# VDA.net
KiCad netlist of a schematic drawn in EAGLE
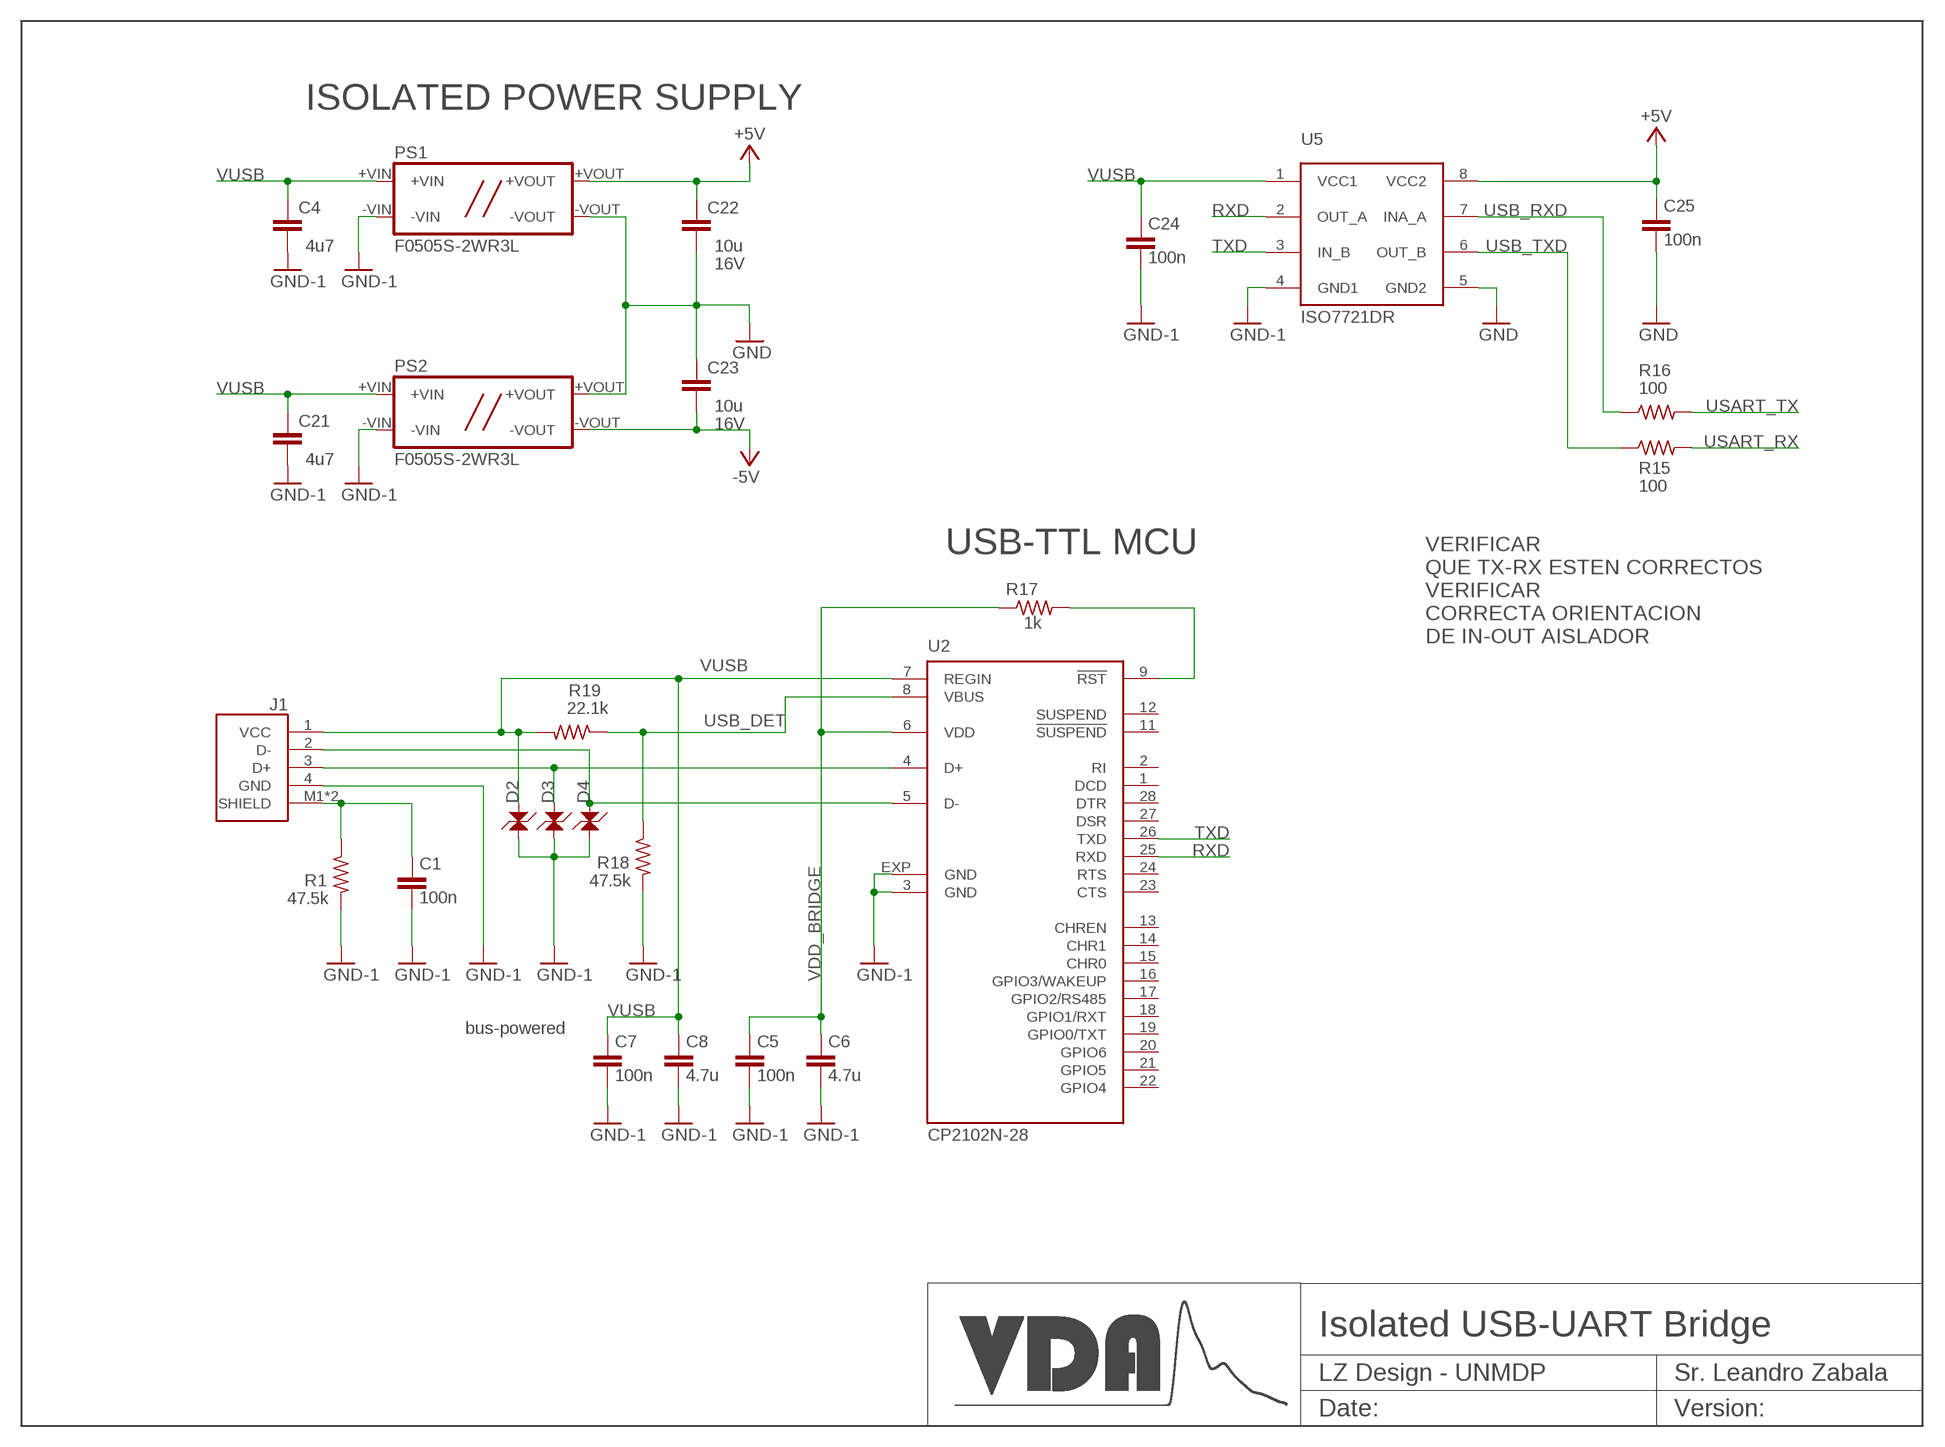
[diagram p0: schematic, sheet 1]
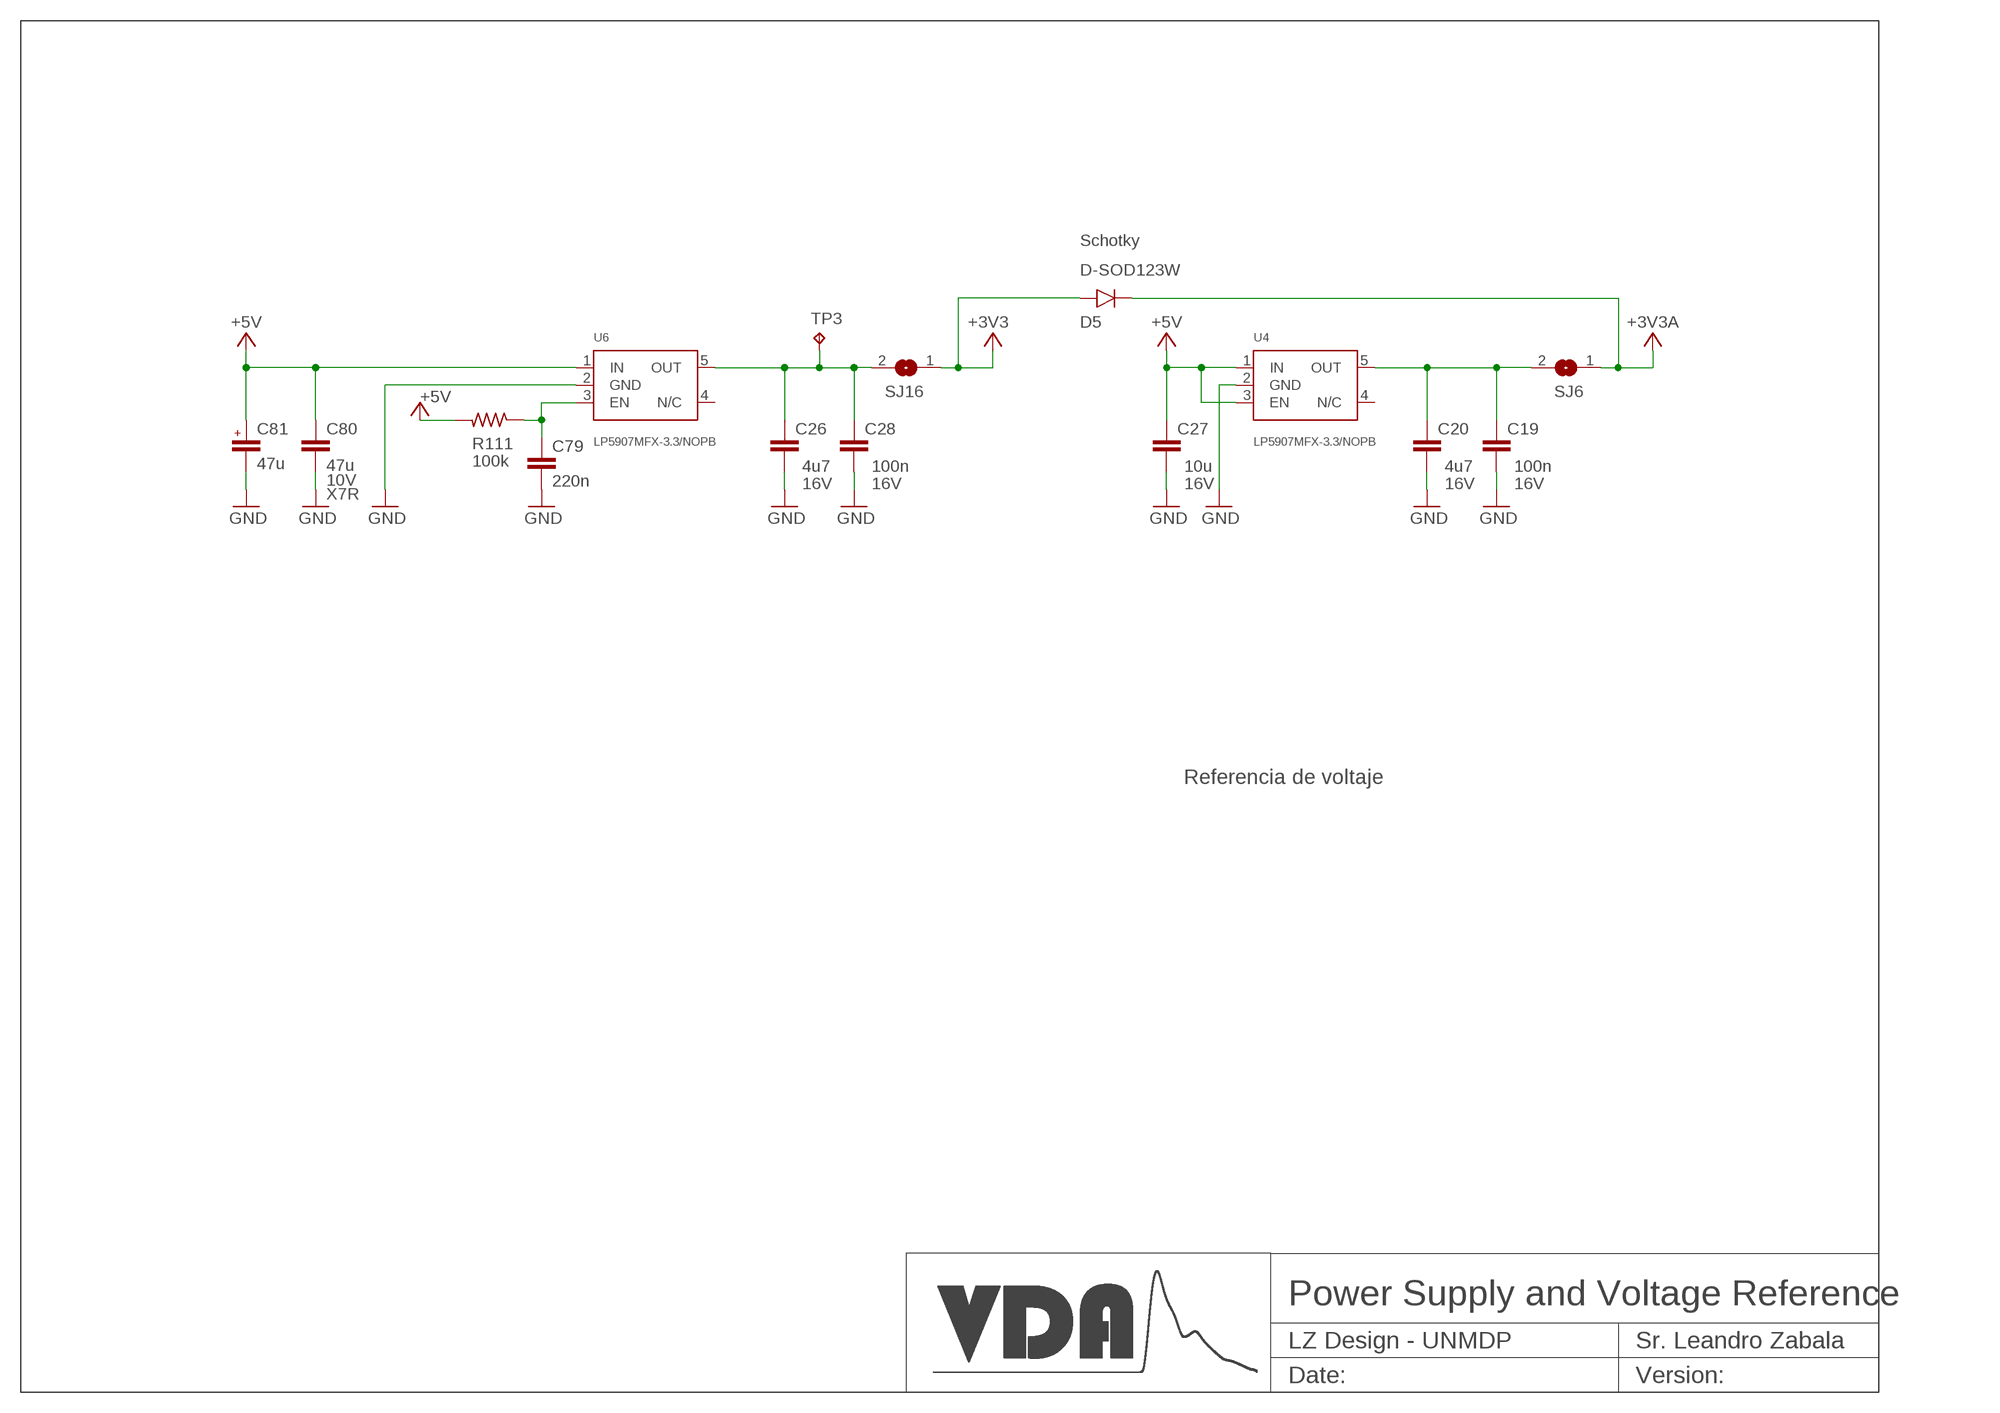
[diagram p1: schematic, sheet 2]
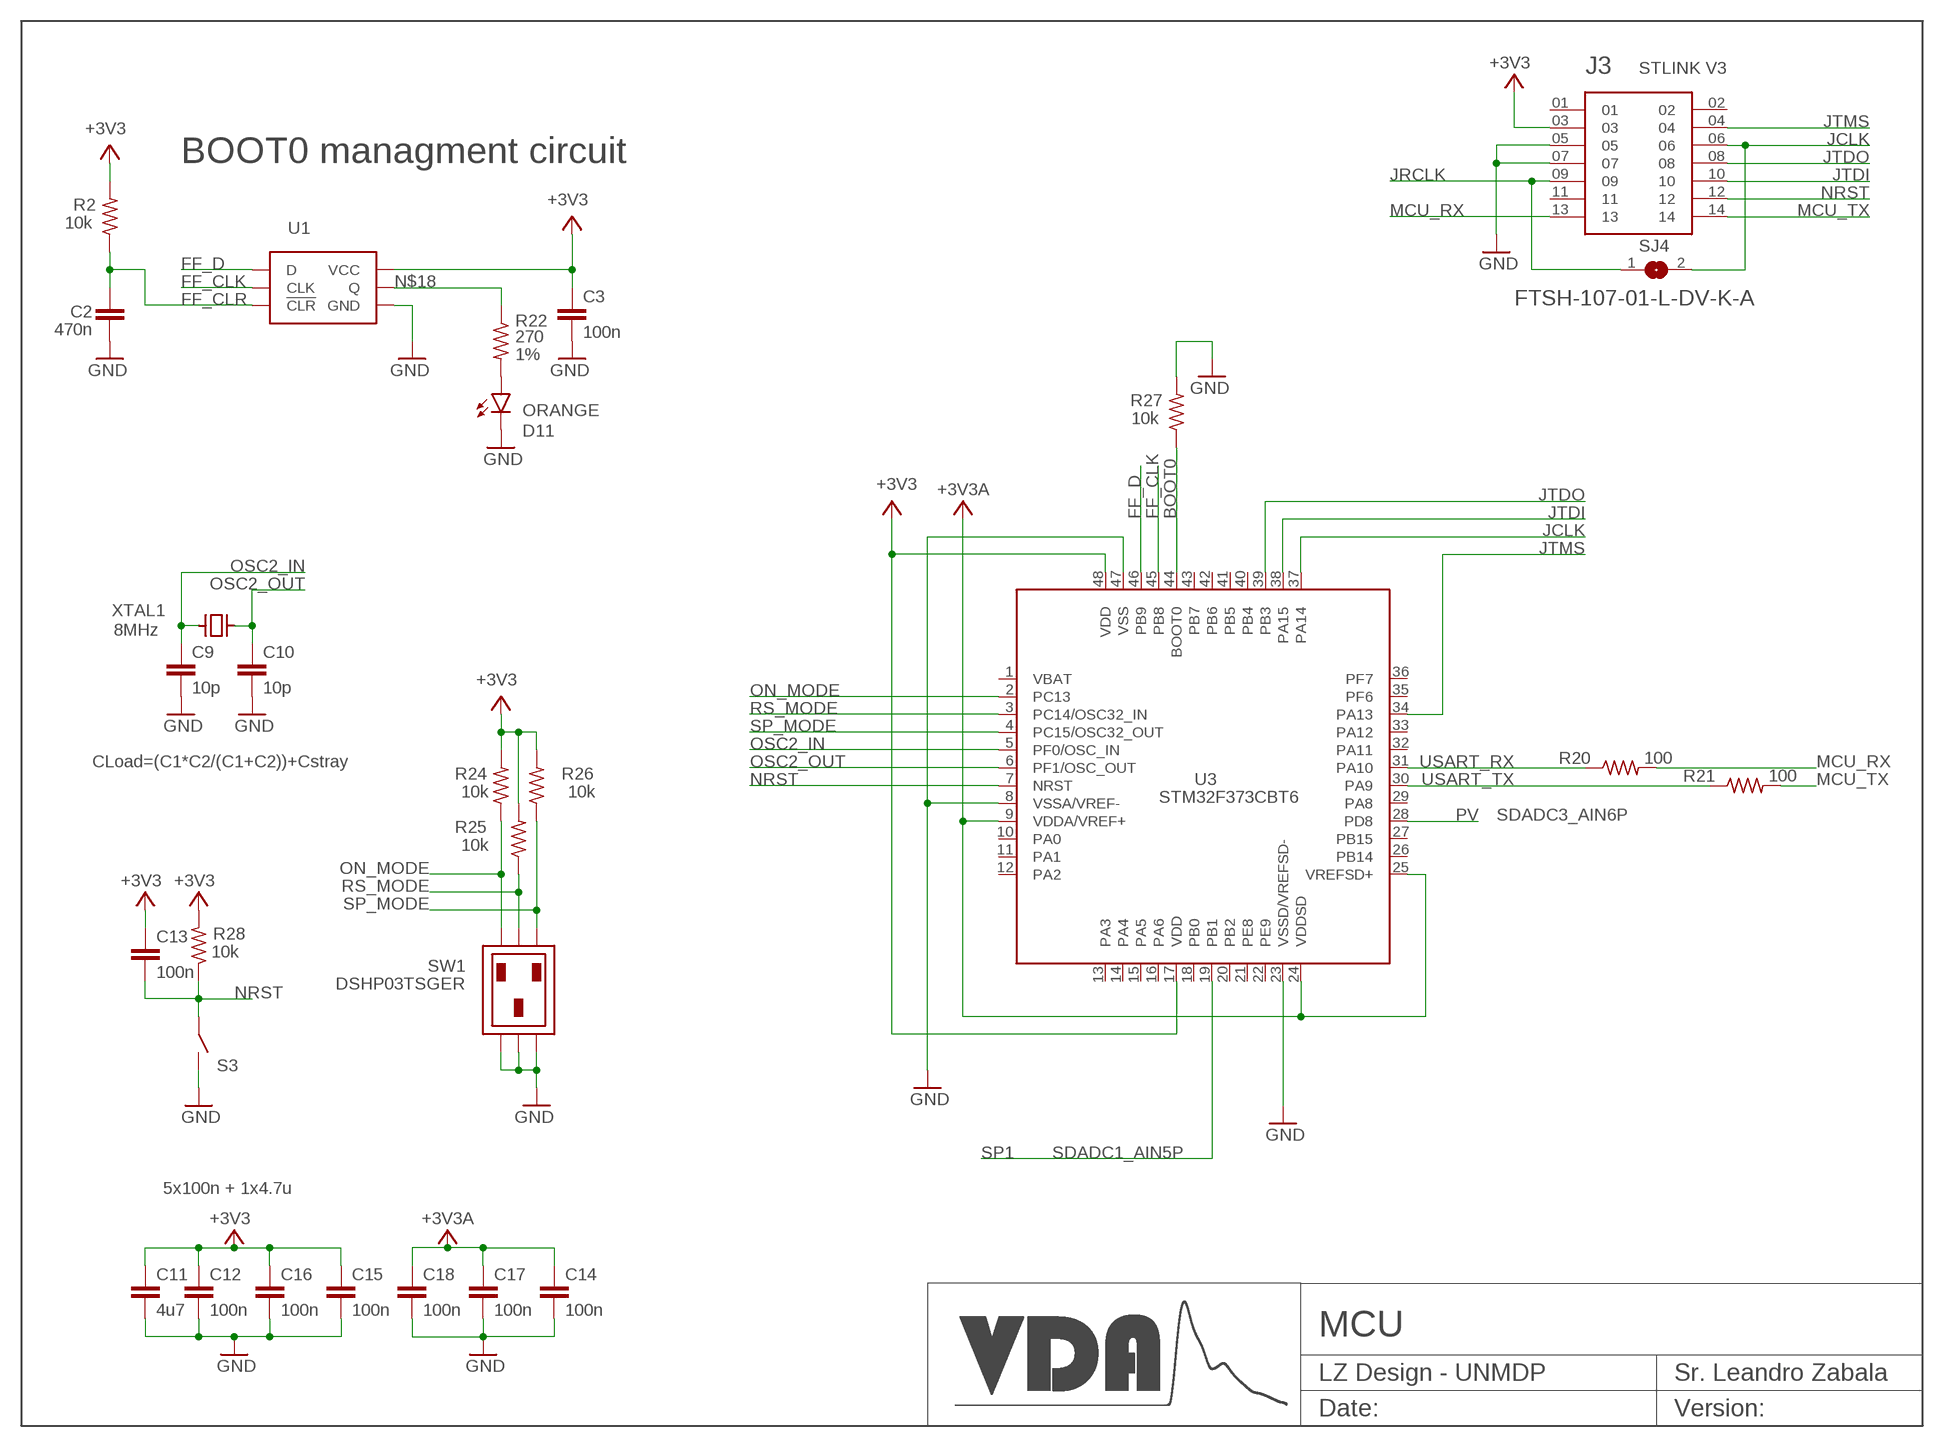
[diagram p2: schematic, sheet 3]
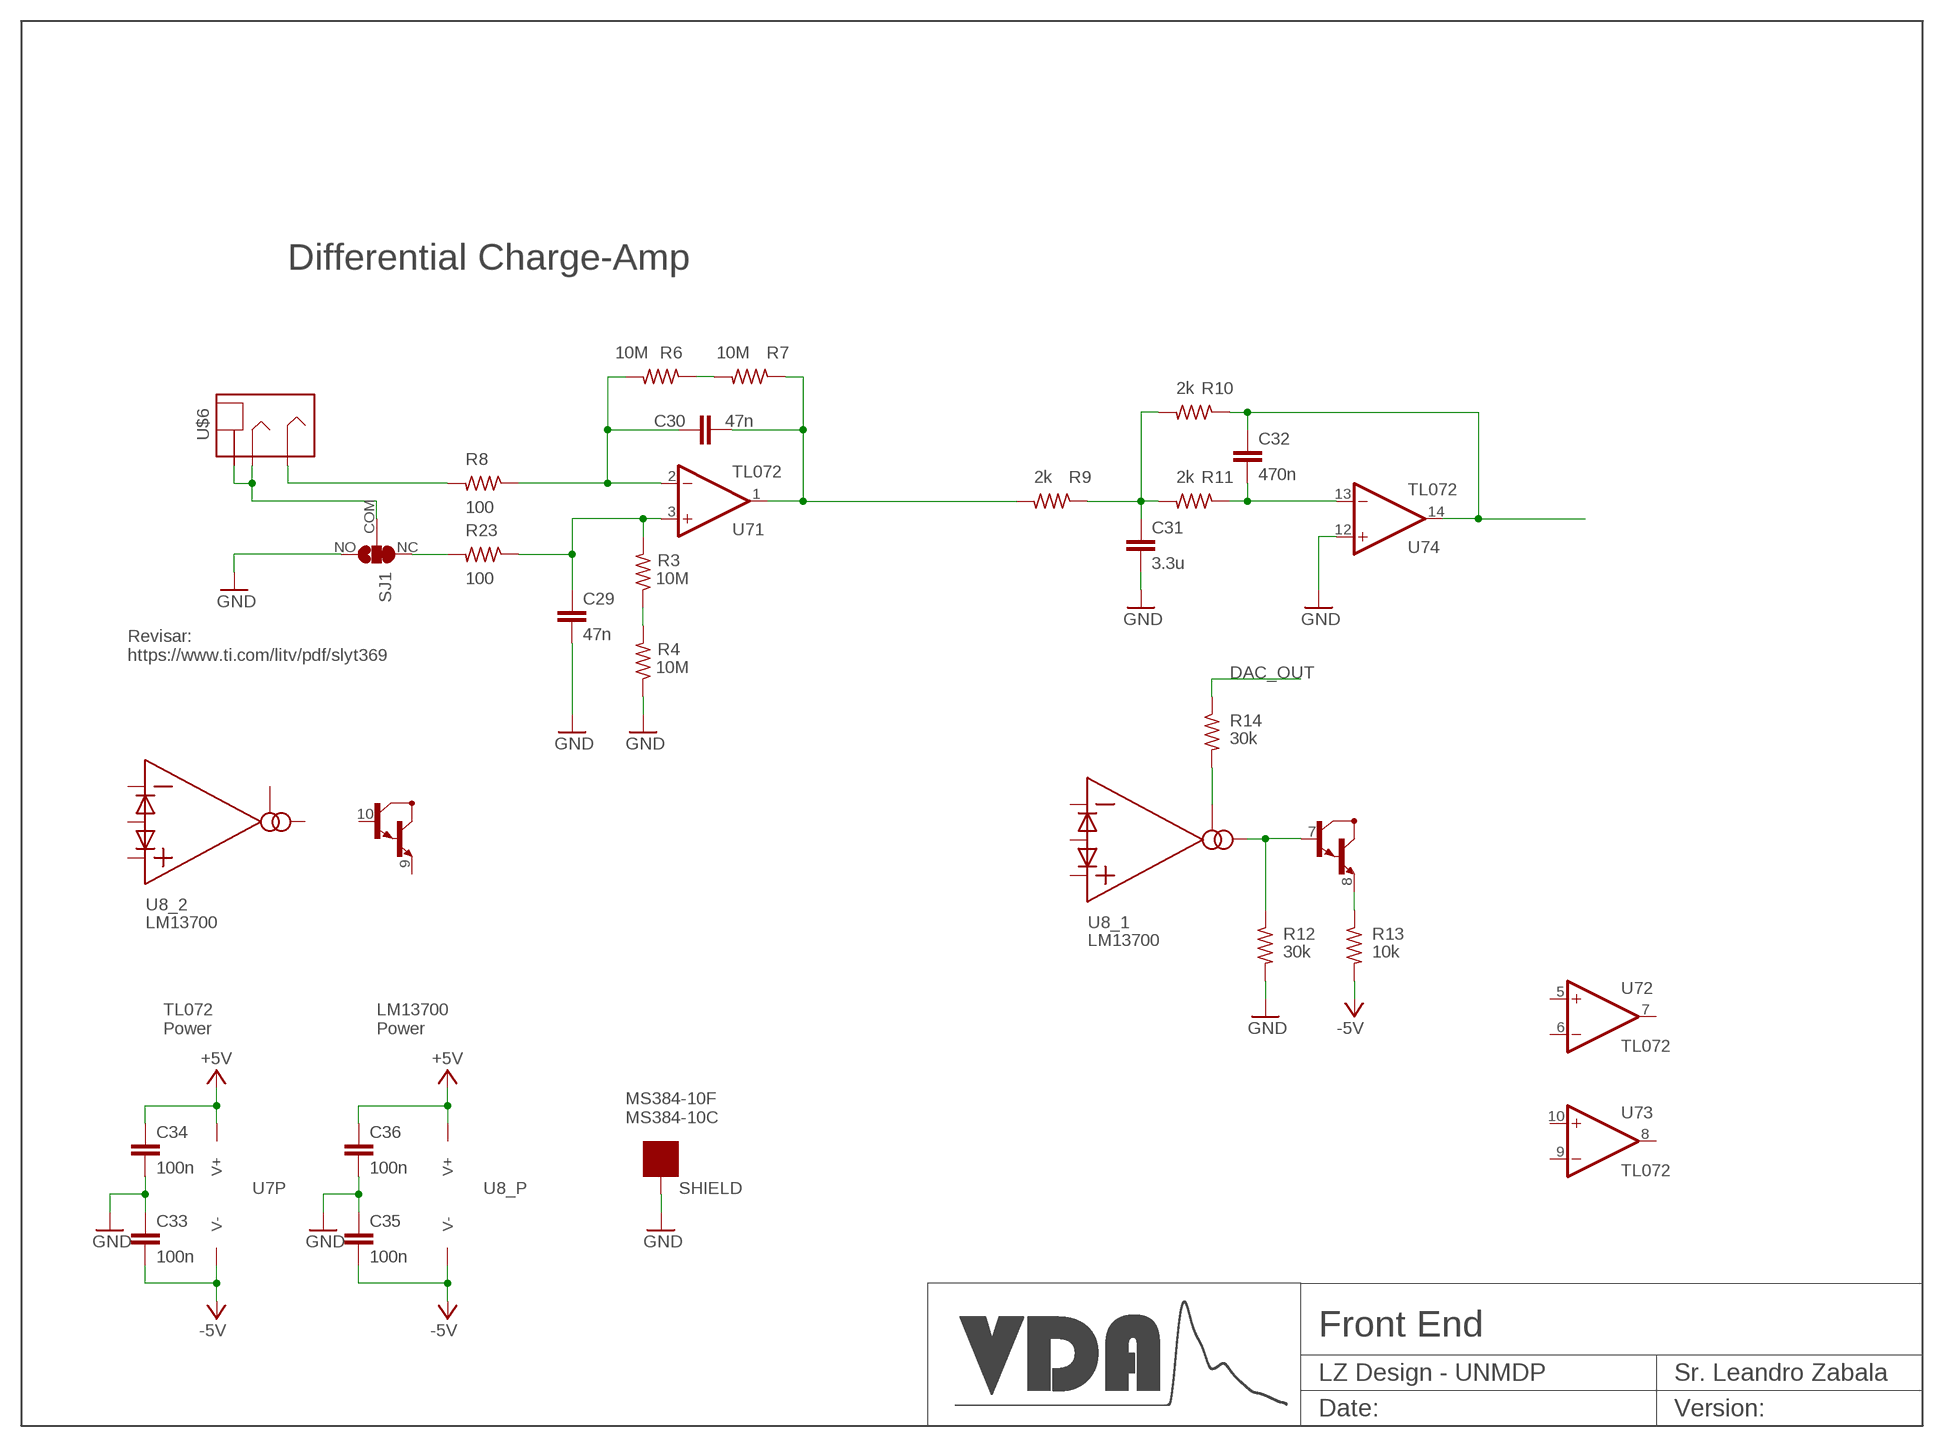
[diagram p3: schematic, sheet 4]
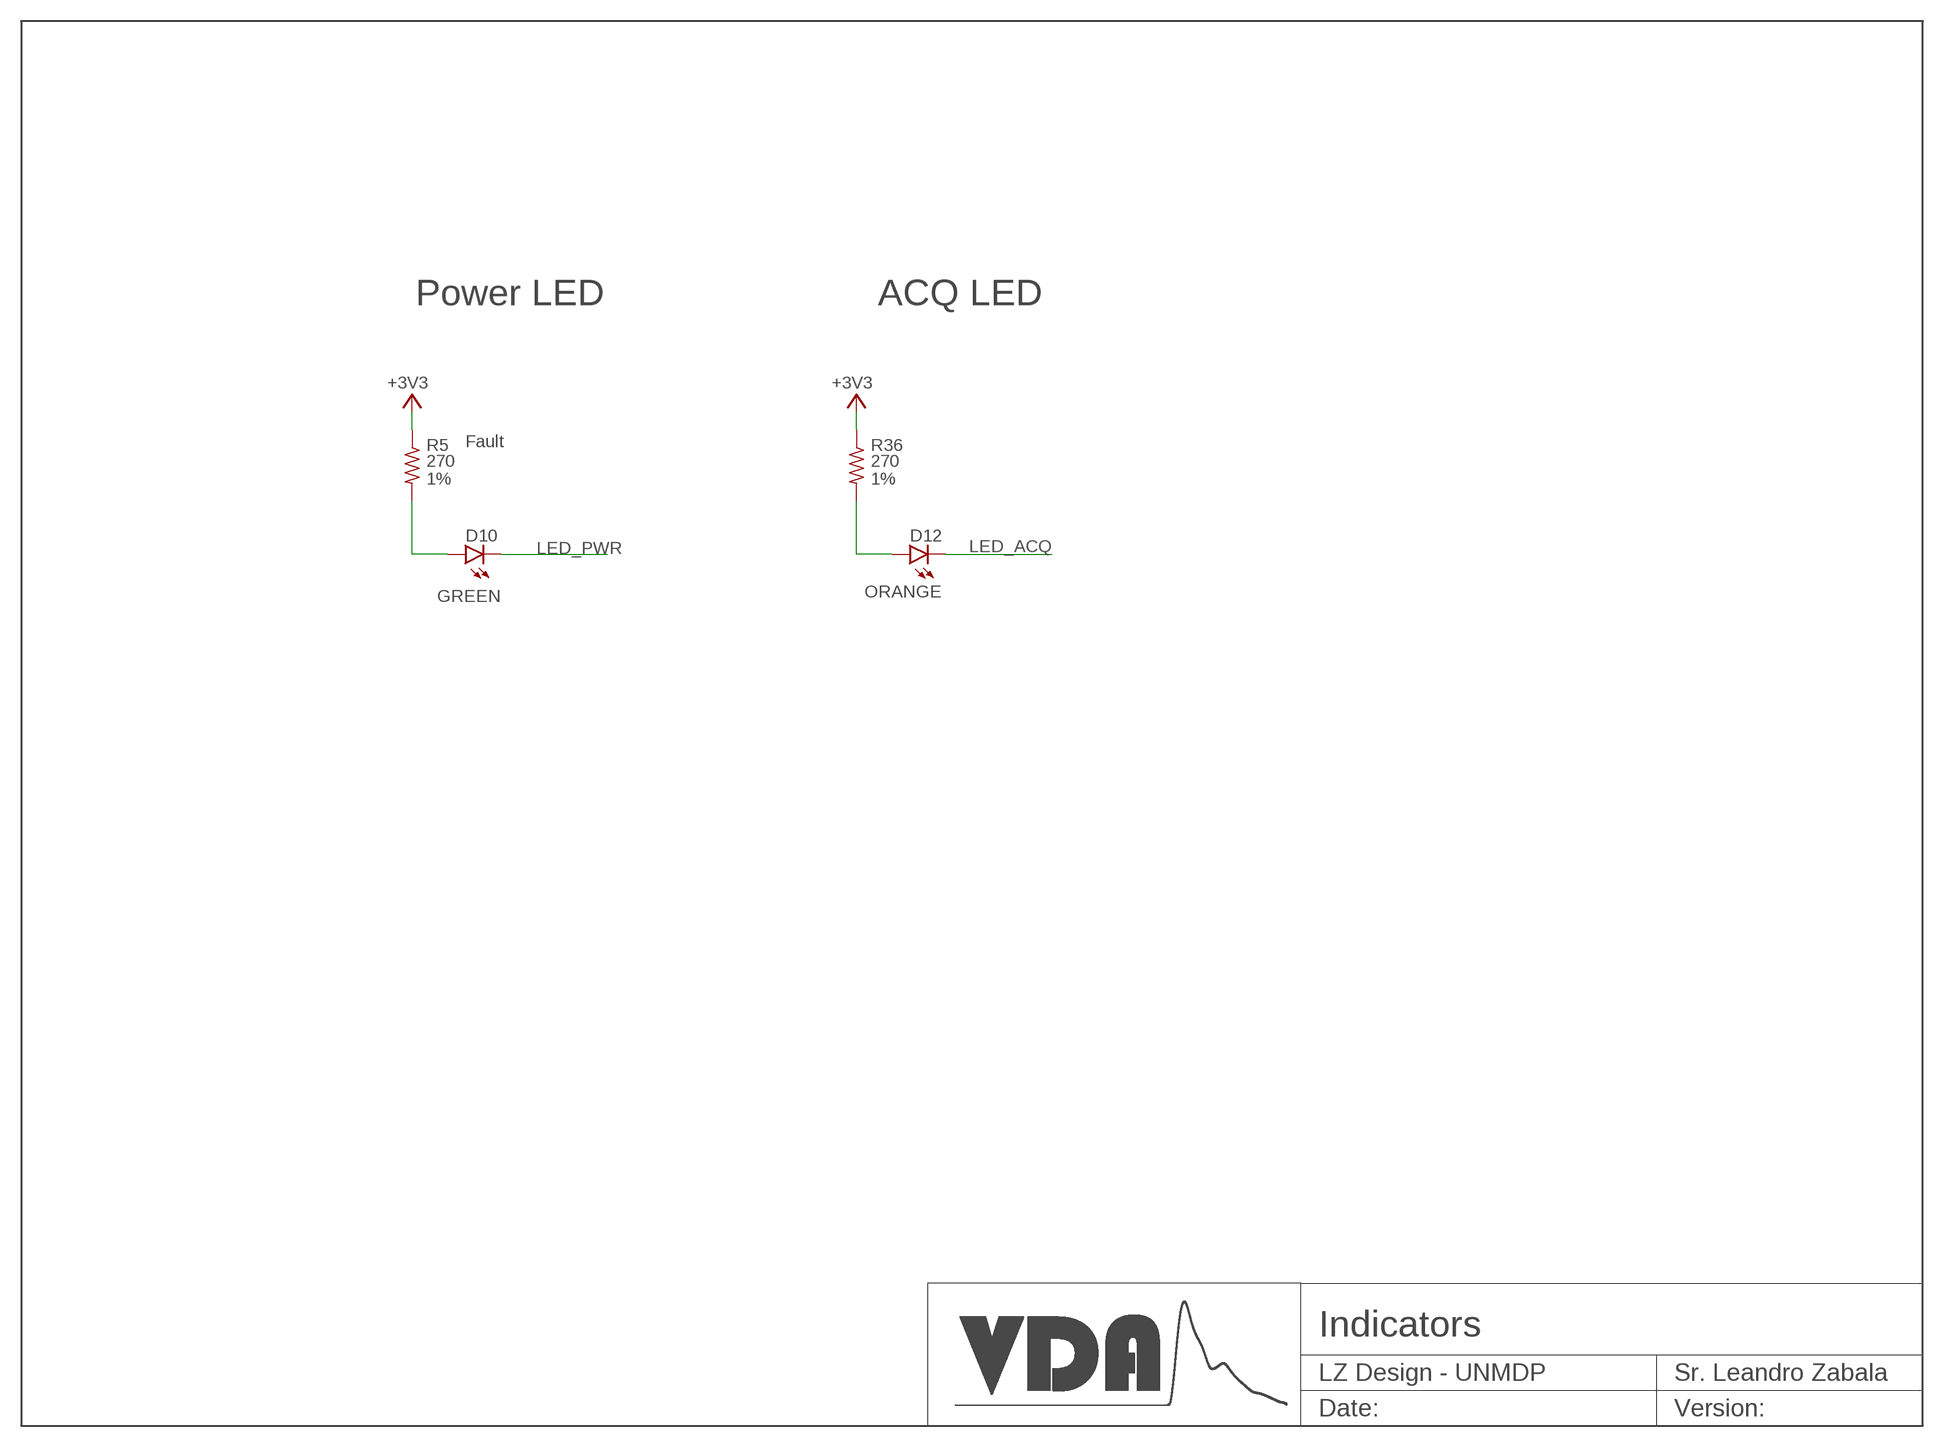
[diagram p4: schematic, sheet 5]

(export (version "E")
  (design (tool "Eeschema 10.0.6"))
  (components
    (comp (ref "D10")
      (value "GREEN")
      (footprint "eagle-import:LED_0603_ARROW")
      (libsource (lib "eagle-import") (part "LED_0603_ARROW"))
    )
    (comp (ref "D12")
      (value "ORANGE")
      (footprint "eagle-import:LED_0603_ARROW")
      (libsource (lib "eagle-import") (part "LED_0603_ARROW"))
    )
    (comp (ref "R5")
      (value "270")
      (footprint "eagle-import:R_0402")
      (fields (field (name "TOL") "1%"))
      (libsource (lib "eagle-import") (part "R_0402"))
    )
    (comp (ref "R36")
      (value "270")
      (footprint "eagle-import:R_0402")
      (fields (field (name "TOL") "1%"))
      (libsource (lib "eagle-import") (part "R_0402"))
    )
    (comp (ref "C1")
      (value "100n")
      (footprint "eagle-import:C_0603")
      (libsource (lib "eagle-import") (part "C_0603"))
    )
    (comp (ref "C4")
      (value "4u7")
      (footprint "eagle-import:C_0603")
      (fields (field (name "V") "16V"))
      (libsource (lib "eagle-import") (part "C_0603"))
    )
    (comp (ref "C5")
      (value "100n")
      (footprint "eagle-import:C_0603")
      (libsource (lib "eagle-import") (part "C_0603"))
    )
    (comp (ref "C6")
      (value "4.7u")
      (footprint "eagle-import:C_0805")
      (libsource (lib "eagle-import") (part "C_0805"))
    )
    (comp (ref "C7")
      (value "100n")
      (footprint "eagle-import:C_0603")
      (libsource (lib "eagle-import") (part "C_0603"))
    )
    (comp (ref "C8")
      (value "4.7u")
      (footprint "eagle-import:C_0805")
      (libsource (lib "eagle-import") (part "C_0805"))
    )
    (comp (ref "C21")
      (value "4u7")
      (footprint "eagle-import:C_0603")
      (fields (field (name "V") "16V"))
      (libsource (lib "eagle-import") (part "C_0603"))
    )
    (comp (ref "C22")
      (value "10u")
      (footprint "eagle-import:C_0603")
      (fields (field (name "V") "16V"))
      (libsource (lib "eagle-import") (part "C_0603"))
    )
    (comp (ref "C23")
      (value "10u")
      (footprint "eagle-import:C_0603")
      (fields (field (name "V") "16V"))
      (libsource (lib "eagle-import") (part "C_0603"))
    )
    (comp (ref "C24")
      (value "100n")
      (footprint "eagle-import:C_0603")
      (libsource (lib "eagle-import") (part "C_0603"))
    )
    (comp (ref "C25")
      (value "100n")
      (footprint "eagle-import:C_0603")
      (libsource (lib "eagle-import") (part "C_0603"))
    )
    (comp (ref "D2")
      (value "LESD5D5.0CT1G")
      (footprint "eagle-import:SOD523")
      (libsource (lib "eagle-import") (part "LESD5D5.0CT1G"))
    )
    (comp (ref "D3")
      (value "LESD5D5.0CT1G")
      (footprint "eagle-import:SOD523")
      (libsource (lib "eagle-import") (part "LESD5D5.0CT1G"))
    )
    (comp (ref "D4")
      (value "LESD5D5.0CT1G")
      (footprint "eagle-import:SOD523")
      (libsource (lib "eagle-import") (part "LESD5D5.0CT1G"))
    )
    (comp (ref "J1")
      (value "USB-2.0")
      (footprint "eagle-import:USB-B")
      (libsource (lib "eagle-import") (part "USB-2.0"))
    )
    (comp (ref "PS1")
      (value "F0505S-2WR3L")
      (footprint "eagle-import:0505S-2WR3")
      (libsource (lib "eagle-import") (part "ISOLATED_DCDC"))
    )
    (comp (ref "PS2")
      (value "F0505S-2WR3L")
      (footprint "eagle-import:0505S-2WR3")
      (libsource (lib "eagle-import") (part "ISOLATED_DCDC"))
    )
    (comp (ref "R1")
      (value "47.5k")
      (footprint "eagle-import:R0402")
      (libsource (lib "eagle-import") (part "R-US_R0402"))
    )
    (comp (ref "R15")
      (value "100")
      (footprint "eagle-import:R_0603")
      (libsource (lib "eagle-import") (part "R_0603"))
    )
    (comp (ref "R16")
      (value "100")
      (footprint "eagle-import:R_0603")
      (libsource (lib "eagle-import") (part "R_0603"))
    )
    (comp (ref "R17")
      (value "1k")
      (footprint "eagle-import:R0402")
      (libsource (lib "eagle-import") (part "R-US_R0402"))
    )
    (comp (ref "R18")
      (value "47.5k")
      (footprint "eagle-import:R0402")
      (libsource (lib "eagle-import") (part "R-US_R0402"))
    )
    (comp (ref "R19")
      (value "22.1k")
      (footprint "eagle-import:R0402")
      (libsource (lib "eagle-import") (part "R-US_R0402"))
    )
    (comp (ref "U2")
      (value "CP2102N-28")
      (footprint "eagle-import:MLP28")
      (libsource (lib "eagle-import") (part "CP2102N-28"))
    )
    (comp (ref "U5")
      (value "ISO7721DR")
      (footprint "eagle-import:SO8")
      (libsource (lib "eagle-import") (part "ISO7721DR"))
    )
    (comp (ref "C2")
      (value "470n")
      (footprint "eagle-import:C_0603")
      (libsource (lib "eagle-import") (part "C_0603"))
    )
    (comp (ref "C3")
      (value "100n")
      (footprint "eagle-import:C_0603")
      (libsource (lib "eagle-import") (part "C_0603"))
    )
    (comp (ref "C9")
      (value "10p")
      (footprint "eagle-import:C_0603")
      (libsource (lib "eagle-import") (part "C_0603"))
    )
    (comp (ref "C10")
      (value "10p")
      (footprint "eagle-import:C_0603")
      (libsource (lib "eagle-import") (part "C_0603"))
    )
    (comp (ref "C11")
      (value "4u7")
      (footprint "eagle-import:C_0805")
      (libsource (lib "eagle-import") (part "C_0805"))
    )
    (comp (ref "C12")
      (value "100n")
      (footprint "eagle-import:C_0603")
      (libsource (lib "eagle-import") (part "C_0603"))
    )
    (comp (ref "C13")
      (value "100n")
      (footprint "eagle-import:C_0603")
      (libsource (lib "eagle-import") (part "C_0603"))
    )
    (comp (ref "C14")
      (value "100n")
      (footprint "eagle-import:C_0603")
      (libsource (lib "eagle-import") (part "C_0603"))
    )
    (comp (ref "C15")
      (value "100n")
      (footprint "eagle-import:C_0603")
      (libsource (lib "eagle-import") (part "C_0603"))
    )
    (comp (ref "C16")
      (value "100n")
      (footprint "eagle-import:C_0603")
      (libsource (lib "eagle-import") (part "C_0603"))
    )
    (comp (ref "C17")
      (value "100n")
      (footprint "eagle-import:C_0603")
      (libsource (lib "eagle-import") (part "C_0603"))
    )
    (comp (ref "C18")
      (value "100n")
      (footprint "eagle-import:C_0603")
      (libsource (lib "eagle-import") (part "C_0603"))
    )
    (comp (ref "D11")
      (value "ORANGE")
      (footprint "eagle-import:LED_0603_ARROW")
      (libsource (lib "eagle-import") (part "LED_0603_ARROW"))
    )
    (comp (ref "J3")
      (value "FTSH-107-01-L-DV-K-A")
      (footprint "eagle-import:SAMTEC_FTSH-107-01-L-DV-K-A")
      (fields (field (name "MANUFACTURER") "Samtec"))
      (libsource (lib "eagle-import") (part "FTSH-107-01-L-DV-K-A"))
    )
    (comp (ref "R2")
      (value "10k")
      (footprint "eagle-import:R_0603")
      (libsource (lib "eagle-import") (part "R_0603"))
    )
    (comp (ref "R20")
      (value "100")
      (footprint "eagle-import:R_0603")
      (libsource (lib "eagle-import") (part "R_0603"))
    )
    (comp (ref "R21")
      (value "100")
      (footprint "eagle-import:R_0603")
      (libsource (lib "eagle-import") (part "R_0603"))
    )
    (comp (ref "R22")
      (value "270")
      (footprint "eagle-import:R_0402")
      (fields (field (name "TOL") "1%"))
      (libsource (lib "eagle-import") (part "R_0402"))
    )
    (comp (ref "R24")
      (value "10k")
      (footprint "eagle-import:R_0603")
      (libsource (lib "eagle-import") (part "R_0603"))
    )
    (comp (ref "R25")
      (value "10k")
      (footprint "eagle-import:R_0603")
      (libsource (lib "eagle-import") (part "R_0603"))
    )
    (comp (ref "R26")
      (value "10k")
      (footprint "eagle-import:R_0603")
      (libsource (lib "eagle-import") (part "R_0603"))
    )
    (comp (ref "R27")
      (value "10k")
      (footprint "eagle-import:R_0603")
      (libsource (lib "eagle-import") (part "R_0603"))
    )
    (comp (ref "R28")
      (value "10k")
      (footprint "eagle-import:R_0603")
      (libsource (lib "eagle-import") (part "R_0603"))
    )
    (comp (ref "S3")
      (value "TSWITCH_SMTR2")
      (footprint "eagle-import:SMTR2")
      (libsource (lib "eagle-import") (part "TSWITCH_SMTR2"))
    )
    (comp (ref "SJ4") (value "SJ") (footprint "eagle-import:SJ") (libsource (lib "eagle-import") (part "SJ")))
    (comp (ref "SW1")
      (value "DSHP03TSGER")
      (footprint "eagle-import:DIPSW-3")
      (libsource (lib "eagle-import") (part "DIPSW-3"))
    )
    (comp (ref "U1")
      (value "SN74LVC1G175")
      (footprint "eagle-import:SOT-23-6")
      (libsource (lib "eagle-import") (part "SN74LVC1G175"))
    )
    (comp (ref "U3")
      (value "STM32F373CBT6")
      (footprint "eagle-import:QFP50P900X900X160-48N")
      (libsource (lib "eagle-import") (part "STM32F373-48CT"))
    )
    (comp (ref "XTAL1")
      (value "8MHz")
      (footprint "eagle-import:XTAL3.2X2.5")
      (fields (field (name "MPN") "830108313809"))
      (libsource (lib "eagle-import") (part "XTAL3.2X2.5"))
    )
    (comp (ref "C29")
      (value "47n")
      (footprint "eagle-import:C_0603")
      (libsource (lib "eagle-import") (part "C_0603"))
    )
    (comp (ref "C30")
      (value "47n")
      (footprint "eagle-import:C_0603")
      (libsource (lib "eagle-import") (part "C_0603"))
    )
    (comp (ref "C31")
      (value "3.3u")
      (footprint "eagle-import:C_0603")
      (libsource (lib "eagle-import") (part "C_0603"))
    )
    (comp (ref "C32")
      (value "470n")
      (footprint "eagle-import:C_0603")
      (libsource (lib "eagle-import") (part "C_0603"))
    )
    (comp (ref "C33")
      (value "100n")
      (footprint "eagle-import:C_0603")
      (libsource (lib "eagle-import") (part "C_0603"))
    )
    (comp (ref "C34")
      (value "100n")
      (footprint "eagle-import:C_0603")
      (libsource (lib "eagle-import") (part "C_0603"))
    )
    (comp (ref "C35")
      (value "100n")
      (footprint "eagle-import:C_0603")
      (libsource (lib "eagle-import") (part "C_0603"))
    )
    (comp (ref "C36")
      (value "100n")
      (footprint "eagle-import:C_0603")
      (libsource (lib "eagle-import") (part "C_0603"))
    )
    (comp (ref "R3")
      (value "10M")
      (footprint "eagle-import:R_0603")
      (libsource (lib "eagle-import") (part "R_0603"))
    )
    (comp (ref "R4")
      (value "10M")
      (footprint "eagle-import:R_0603")
      (libsource (lib "eagle-import") (part "R_0603"))
    )
    (comp (ref "R6")
      (value "10M")
      (footprint "eagle-import:R_0603")
      (libsource (lib "eagle-import") (part "R_0603"))
    )
    (comp (ref "R7")
      (value "10M")
      (footprint "eagle-import:R_0603")
      (libsource (lib "eagle-import") (part "R_0603"))
    )
    (comp (ref "R8")
      (value "100")
      (footprint "eagle-import:R_0603")
      (libsource (lib "eagle-import") (part "R_0603"))
    )
    (comp (ref "R9")
      (value "2k")
      (footprint "eagle-import:R_0603")
      (libsource (lib "eagle-import") (part "R_0603"))
    )
    (comp (ref "R10")
      (value "2k")
      (footprint "eagle-import:R_0603")
      (libsource (lib "eagle-import") (part "R_0603"))
    )
    (comp (ref "R11")
      (value "2k")
      (footprint "eagle-import:R_0603")
      (libsource (lib "eagle-import") (part "R_0603"))
    )
    (comp (ref "R12")
      (value "30k")
      (footprint "eagle-import:R_0603")
      (libsource (lib "eagle-import") (part "R_0603"))
    )
    (comp (ref "R13")
      (value "10k")
      (footprint "eagle-import:R_0603")
      (libsource (lib "eagle-import") (part "R_0603"))
    )
    (comp (ref "R14")
      (value "30k")
      (footprint "eagle-import:R_0603")
      (libsource (lib "eagle-import") (part "R_0603"))
    )
    (comp (ref "R23")
      (value "100")
      (footprint "eagle-import:R_0603")
      (libsource (lib "eagle-import") (part "R_0603"))
    )
    (comp (ref "SHIELD")
      (value "MS384")
      (footprint "eagle-import:MS384")
      (libsource (lib "eagle-import") (part "MS384"))
    )
    (comp (ref "SJ1")
      (value "SJ-PS")
      (footprint "eagle-import:SJ_2")
      (libsource (lib "eagle-import") (part "SJ-PS"))
    )
    (comp (ref "U$6")
      (value "STEREO-JACK")
      (footprint "eagle-import:PJ-3200")
      (libsource (lib "eagle-import") (part "STEREO-JACK"))
    )
    (comp (ref "U7")
      (value "TL072")
      (footprint "eagle-import:SOIC127P600X175-14N")
      (libsource (lib "eagle-import") (part "LM324BD"))
    )
    (comp (ref "U8")
      (value "LM13700")
      (footprint "eagle-import:SO16")
      (libsource (lib "eagle-import") (part "LM13700"))
    )
    (comp (ref "C19")
      (value "100n")
      (footprint "eagle-import:C_0603")
      (fields (field (name "V") "16V"))
      (libsource (lib "eagle-import") (part "C_0603"))
    )
    (comp (ref "C20")
      (value "4u7")
      (footprint "eagle-import:C_0603")
      (fields (field (name "V") "16V"))
      (libsource (lib "eagle-import") (part "C_0603"))
    )
    (comp (ref "C26")
      (value "4u7")
      (footprint "eagle-import:C_0603")
      (fields (field (name "V") "16V"))
      (libsource (lib "eagle-import") (part "C_0603"))
    )
    (comp (ref "C27")
      (value "10u")
      (footprint "eagle-import:C_0603")
      (fields (field (name "V") "16V"))
      (libsource (lib "eagle-import") (part "C_0603"))
    )
    (comp (ref "C28")
      (value "100n")
      (footprint "eagle-import:C_0603")
      (fields (field (name "V") "16V"))
      (libsource (lib "eagle-import") (part "C_0603"))
    )
    (comp (ref "C79")
      (value "220n")
      (footprint "eagle-import:C_0603")
      (libsource (lib "eagle-import") (part "C_0603"))
    )
    (comp (ref "C80")
      (value "47u")
      (footprint "eagle-import:C_1206")
      (fields (field (name "D") "X7R") (field (name "ESR") "LOW") (field (name "V") "10V"))
      (libsource (lib "eagle-import") (part "C_1206"))
    )
    (comp (ref "C81")
      (value "47u")
      (footprint "eagle-import:A_3216")
      (libsource (lib "eagle-import") (part "C-TANTALUM_A_3216"))
    )
    (comp (ref "D5")
      (value "D-SOD123W")
      (footprint "eagle-import:SOD123W")
      (fields (field (name "TYPE") "Schotky"))
      (libsource (lib "eagle-import") (part "D-SOD123W"))
    )
    (comp (ref "R111")
      (value "100k")
      (footprint "eagle-import:R_0603")
      (libsource (lib "eagle-import") (part "R_0603"))
    )
    (comp (ref "SJ6") (value "SJ") (footprint "eagle-import:SJ") (libsource (lib "eagle-import") (part "SJ")))
    (comp (ref "SJ16")
      (value "SJ")
      (footprint "eagle-import:SJ")
      (libsource (lib "eagle-import") (part "SJ"))
    )
    (comp (ref "TP3")
      (value "TPB1,27")
      (footprint "eagle-import:B1,27")
      (libsource (lib "eagle-import") (part "TPB1,27"))
    )
    (comp (ref "U4")
      (value "LP5907MFX-3.3/NOPB")
      (footprint "eagle-import:SOT23-5")
      (libsource (lib "eagle-import") (part "LDO1SOT23-5_1"))
    )
    (comp (ref "U6")
      (value "LP5907MFX-3.3/NOPB")
      (footprint "eagle-import:SOT23-5")
      (libsource (lib "eagle-import") (part "LDO1SOT23-5_1"))
    )
  )
  (nets
    (net (code "1") (name "+3V3") (class "Default")
      (node (ref "C11") (pin "P$1") (pinfunction "1_P$1") (pintype "passive"))
      (node (ref "C12") (pin "P$1") (pinfunction "1_P$1") (pintype "passive"))
      (node (ref "C13") (pin "P$1") (pinfunction "1_P$1") (pintype "passive"))
      (node (ref "C15") (pin "P$1") (pinfunction "1_P$1") (pintype "passive"))
      (node (ref "C16") (pin "P$1") (pinfunction "1_P$1") (pintype "passive"))
      (node (ref "C3") (pin "P$1") (pinfunction "1_P$1") (pintype "passive"))
      (node (ref "D5") (pin "A") (pinfunction "A_A") (pintype "bidirectional"))
      (node (ref "J3") (pin "03") (pinfunction "03_03") (pintype "passive"))
      (node (ref "R2") (pin "2") (pinfunction "2_2") (pintype "passive"))
      (node (ref "R24") (pin "2") (pinfunction "2_2") (pintype "passive"))
      (node (ref "R25") (pin "2") (pinfunction "2_2") (pintype "passive"))
      (node (ref "R26") (pin "2") (pinfunction "2_2") (pintype "passive"))
      (node (ref "R28") (pin "2") (pinfunction "2_2") (pintype "passive"))
      (node (ref "R36") (pin "1") (pinfunction "1_1") (pintype "passive"))
      (node (ref "R5") (pin "1") (pinfunction "1_1") (pintype "passive"))
      (node (ref "SJ16") (pin "1") (pinfunction "1_1") (pintype "passive"))
      (node (ref "U1") (pin "5") (pinfunction "VCC_5") (pintype "power_in"))
      (node (ref "U3") (pin "17") (pinfunction "VDD_17") (pintype "power_in"))
      (node (ref "U3") (pin "48") (pinfunction "VDD_48") (pintype "power_in"))
    )
    (net (code "2") (name "+3V3A") (class "Default")
      (node (ref "C14") (pin "P$1") (pinfunction "1_P$1") (pintype "passive"))
      (node (ref "C17") (pin "P$1") (pinfunction "1_P$1") (pintype "passive"))
      (node (ref "C18") (pin "P$1") (pinfunction "1_P$1") (pintype "passive"))
      (node (ref "D5") (pin "C") (pinfunction "K_C") (pintype "bidirectional"))
      (node (ref "SJ6") (pin "1") (pinfunction "1_1") (pintype "passive"))
      (node (ref "U3") (pin "24") (pinfunction "VDDSD_24") (pintype "power_in"))
      (node (ref "U3") (pin "25") (pinfunction "VREFSD+_25") (pintype "input"))
      (node (ref "U3") (pin "9") (pinfunction "VDDA/VREF+_9") (pintype "input"))
    )
    (net (code "3") (name "+5V") (class "Default")
      (node (ref "C22") (pin "P$1") (pinfunction "1_P$1") (pintype "passive"))
      (node (ref "C25") (pin "P$1") (pinfunction "1_P$1") (pintype "passive"))
      (node (ref "C27") (pin "P$1") (pinfunction "1_P$1") (pintype "passive"))
      (node (ref "C34") (pin "P$1") (pinfunction "1_P$1") (pintype "passive"))
      (node (ref "C36") (pin "P$1") (pinfunction "1_P$1") (pintype "passive"))
      (node (ref "C80") (pin "P$1") (pinfunction "1_P$1") (pintype "passive"))
      (node (ref "C81") (pin "A") (pinfunction "+_A") (pintype "passive"))
      (node (ref "PS1") (pin "+VOUT") (pinfunction "+VOUT_+VOUT") (pintype "passive"))
      (node (ref "R111") (pin "2") (pinfunction "2_2") (pintype "passive"))
      (node (ref "U4") (pin "1") (pinfunction "IN_1") (pintype "power_in"))
      (node (ref "U4") (pin "3") (pinfunction "EN_3") (pintype "input"))
      (node (ref "U5") (pin "8") (pinfunction "VCC2_8") (pintype "power_in"))
      (node (ref "U6") (pin "1") (pinfunction "IN_1") (pintype "power_in"))
      (node (ref "U7") (pin "4") (pinfunction "V+_4") (pintype "power_in"))
      (node (ref "U8") (pin "11") (pinfunction "V+_11") (pintype "power_in"))
    )
    (net (code "4") (name "-5V") (class "Default")
      (node (ref "C23") (pin "P$2") (pinfunction "2_P$2") (pintype "passive"))
      (node (ref "C33") (pin "P$2") (pinfunction "2_P$2") (pintype "passive"))
      (node (ref "C35") (pin "P$2") (pinfunction "2_P$2") (pintype "passive"))
      (node (ref "PS2") (pin "-VOUT") (pinfunction "-VOUT_-VOUT") (pintype "passive"))
      (node (ref "R13") (pin "2") (pinfunction "2_2") (pintype "passive"))
      (node (ref "U7") (pin "11") (pinfunction "V-_11") (pintype "power_in"))
      (node (ref "U8") (pin "6") (pinfunction "V-_6") (pintype "power_in"))
    )
    (net (code "5") (name "BOOT0") (class "Default")
      (node (ref "R27") (pin "1") (pinfunction "1_1") (pintype "passive"))
      (node (ref "U3") (pin "44") (pinfunction "BOOT0_44") (pintype "bidirectional"))
    )
    (net (code "6") (name "DAC_OUT") (class "Default")
      (node (ref "R14") (pin "1") (pinfunction "1_1") (pintype "passive"))
    )
    (net (code "7") (name "FF_CLK") (class "Default")
      (node (ref "U1") (pin "1") (pinfunction "CLK_1") (pintype "input"))
      (node (ref "U3") (pin "45") (pinfunction "PB8_45") (pintype "bidirectional"))
    )
    (net (code "8") (name "FF_CLR") (class "Default")
      (node (ref "C2") (pin "P$1") (pinfunction "1_P$1") (pintype "passive"))
      (node (ref "R2") (pin "1") (pinfunction "1_1") (pintype "passive"))
      (node (ref "U1") (pin "6") (pinfunction "~{CLR}_6") (pintype "input"))
    )
    (net (code "9") (name "FF_D") (class "Default")
      (node (ref "U1") (pin "3") (pinfunction "D_3") (pintype "input"))
      (node (ref "U3") (pin "46") (pinfunction "PB9_46") (pintype "bidirectional"))
    )
    (net (code "10") (name "GND") (class "Default")
      (node (ref "C10") (pin "P$2") (pinfunction "2_P$2") (pintype "passive"))
      (node (ref "C11") (pin "P$2") (pinfunction "2_P$2") (pintype "passive"))
      (node (ref "C12") (pin "P$2") (pinfunction "2_P$2") (pintype "passive"))
      (node (ref "C14") (pin "P$2") (pinfunction "2_P$2") (pintype "passive"))
      (node (ref "C15") (pin "P$2") (pinfunction "2_P$2") (pintype "passive"))
      (node (ref "C16") (pin "P$2") (pinfunction "2_P$2") (pintype "passive"))
      (node (ref "C17") (pin "P$2") (pinfunction "2_P$2") (pintype "passive"))
      (node (ref "C18") (pin "P$2") (pinfunction "2_P$2") (pintype "passive"))
      (node (ref "C19") (pin "P$2") (pinfunction "2_P$2") (pintype "passive"))
      (node (ref "C2") (pin "P$2") (pinfunction "2_P$2") (pintype "passive"))
      (node (ref "C20") (pin "P$2") (pinfunction "2_P$2") (pintype "passive"))
      (node (ref "C22") (pin "P$2") (pinfunction "2_P$2") (pintype "passive"))
      (node (ref "C23") (pin "P$1") (pinfunction "1_P$1") (pintype "passive"))
      (node (ref "C25") (pin "P$2") (pinfunction "2_P$2") (pintype "passive"))
      (node (ref "C26") (pin "P$2") (pinfunction "2_P$2") (pintype "passive"))
      (node (ref "C27") (pin "P$2") (pinfunction "2_P$2") (pintype "passive"))
      (node (ref "C28") (pin "P$2") (pinfunction "2_P$2") (pintype "passive"))
      (node (ref "C29") (pin "P$2") (pinfunction "2_P$2") (pintype "passive"))
      (node (ref "C3") (pin "P$2") (pinfunction "2_P$2") (pintype "passive"))
      (node (ref "C31") (pin "P$2") (pinfunction "2_P$2") (pintype "passive"))
      (node (ref "C33") (pin "P$1") (pinfunction "1_P$1") (pintype "passive"))
      (node (ref "C34") (pin "P$2") (pinfunction "2_P$2") (pintype "passive"))
      (node (ref "C35") (pin "P$1") (pinfunction "1_P$1") (pintype "passive"))
      (node (ref "C36") (pin "P$2") (pinfunction "2_P$2") (pintype "passive"))
      (node (ref "C79") (pin "P$2") (pinfunction "2_P$2") (pintype "passive"))
      (node (ref "C80") (pin "P$2") (pinfunction "2_P$2") (pintype "passive"))
      (node (ref "C81") (pin "K") (pinfunction "-_K") (pintype "passive"))
      (node (ref "C9") (pin "P$2") (pinfunction "2_P$2") (pintype "passive"))
      (node (ref "D11") (pin "K") (pinfunction "K_K") (pintype "passive"))
      (node (ref "J3") (pin "05") (pinfunction "05_05") (pintype "passive"))
      (node (ref "J3") (pin "07") (pinfunction "07_07") (pintype "passive"))
      (node (ref "PS1") (pin "-VOUT") (pinfunction "-VOUT_-VOUT") (pintype "passive"))
      (node (ref "PS2") (pin "+VOUT") (pinfunction "+VOUT_+VOUT") (pintype "passive"))
      (node (ref "R12") (pin "2") (pinfunction "2_2") (pintype "passive"))
      (node (ref "R27") (pin "2") (pinfunction "2_2") (pintype "passive"))
      (node (ref "R4") (pin "1") (pinfunction "1_1") (pintype "passive"))
      (node (ref "S3") (pin "P$3") (pinfunction "P$2_P$3") (pintype "bidirectional"))
      (node (ref "S3") (pin "P$4") (pinfunction "P$2_P$4") (pintype "bidirectional"))
      (node (ref "SHIELD") (pin "P$1") (pinfunction "1_P$1") (pintype "bidirectional"))
      (node (ref "SHIELD") (pin "P$2") (pinfunction "1_P$2") (pintype "bidirectional"))
      (node (ref "SJ1") (pin "NO") (pinfunction "NO_NO") (pintype "passive"))
      (node (ref "SW1") (pin "P$2") (pinfunction "P$2_P$2") (pintype "passive"))
      (node (ref "SW1") (pin "P$4") (pinfunction "P$4_P$4") (pintype "passive"))
      (node (ref "SW1") (pin "P$6") (pinfunction "P$6_P$6") (pintype "passive"))
      (node (ref "U1") (pin "2") (pinfunction "GND_2") (pintype "power_in"))
      (node (ref "U3") (pin "23") (pinfunction "VSSD/VREFSD-_23") (pintype "input"))
      (node (ref "U3") (pin "47") (pinfunction "VSS_47") (pintype "power_in"))
      (node (ref "U3") (pin "8") (pinfunction "VSSA/VREF-_8") (pintype "input"))
      (node (ref "U4") (pin "2") (pinfunction "GND_2") (pintype "power_in"))
      (node (ref "U5") (pin "5") (pinfunction "GND2_5") (pintype "power_in"))
      (node (ref "U6") (pin "2") (pinfunction "GND_2") (pintype "power_in"))
      (node (ref "U7") (pin "12") (pinfunction "+IN_12") (pintype "input"))
    )
    (net (code "11") (name "GND-1") (class "Default")
      (node (ref "C1") (pin "P$2") (pinfunction "2_P$2") (pintype "passive"))
      (node (ref "C21") (pin "P$2") (pinfunction "2_P$2") (pintype "passive"))
      (node (ref "C24") (pin "P$2") (pinfunction "2_P$2") (pintype "passive"))
      (node (ref "C4") (pin "P$2") (pinfunction "2_P$2") (pintype "passive"))
      (node (ref "C5") (pin "P$2") (pinfunction "2_P$2") (pintype "passive"))
      (node (ref "C6") (pin "P$2") (pinfunction "2_P$2") (pintype "passive"))
      (node (ref "C7") (pin "P$2") (pinfunction "2_P$2") (pintype "passive"))
      (node (ref "C8") (pin "P$2") (pinfunction "2_P$2") (pintype "passive"))
      (node (ref "D2") (pin "C") (pinfunction "P$2_C") (pintype "bidirectional"))
      (node (ref "D3") (pin "C") (pinfunction "P$2_C") (pintype "bidirectional"))
      (node (ref "D4") (pin "C") (pinfunction "P$2_C") (pintype "bidirectional"))
      (node (ref "J1") (pin "4") (pinfunction "GND_4") (pintype "power_in"))
      (node (ref "PS1") (pin "-VIN") (pinfunction "-VIN_-VIN") (pintype "passive"))
      (node (ref "PS2") (pin "-VIN") (pinfunction "-VIN_-VIN") (pintype "passive"))
      (node (ref "R1") (pin "2") (pinfunction "2_2") (pintype "passive"))
      (node (ref "R18") (pin "2") (pinfunction "2_2") (pintype "passive"))
      (node (ref "U2") (pin "3") (pinfunction "GND_3") (pintype "power_in"))
      (node (ref "U2") (pin "EXP") (pinfunction "GND_EXP") (pintype "power_in"))
      (node (ref "U5") (pin "4") (pinfunction "GND1_4") (pintype "power_in"))
    )
    (net (code "12") (name "JCLK") (class "Default")
      (node (ref "J3") (pin "06") (pinfunction "06_06") (pintype "passive"))
      (node (ref "SJ4") (pin "2") (pinfunction "2_2") (pintype "passive"))
      (node (ref "U3") (pin "37") (pinfunction "PA14_37") (pintype "bidirectional"))
    )
    (net (code "13") (name "JRCLK") (class "Default")
      (node (ref "J3") (pin "09") (pinfunction "09_09") (pintype "passive"))
      (node (ref "SJ4") (pin "1") (pinfunction "1_1") (pintype "passive"))
    )
    (net (code "14") (name "JTDI") (class "Default")
      (node (ref "J3") (pin "10") (pinfunction "10_10") (pintype "passive"))
      (node (ref "U3") (pin "38") (pinfunction "PA15_38") (pintype "bidirectional"))
    )
    (net (code "15") (name "JTDO") (class "Default")
      (node (ref "J3") (pin "08") (pinfunction "08_08") (pintype "passive"))
      (node (ref "U3") (pin "39") (pinfunction "PB3_39") (pintype "bidirectional"))
    )
    (net (code "16") (name "JTMS") (class "Default")
      (node (ref "J3") (pin "04") (pinfunction "04_04") (pintype "passive"))
      (node (ref "U3") (pin "34") (pinfunction "PA13_34") (pintype "bidirectional"))
    )
    (net (code "17") (name "LED_ACQ") (class "Default")
      (node (ref "D12") (pin "K") (pinfunction "K_K") (pintype "passive"))
    )
    (net (code "18") (name "LED_PWR") (class "Default")
      (node (ref "D10") (pin "K") (pinfunction "K_K") (pintype "passive"))
    )
    (net (code "19") (name "MCU_RX") (class "Default")
      (node (ref "J3") (pin "13") (pinfunction "13_13") (pintype "passive"))
      (node (ref "R20") (pin "2") (pinfunction "2_2") (pintype "passive"))
    )
    (net (code "20") (name "MCU_TX") (class "Default")
      (node (ref "J3") (pin "14") (pinfunction "14_14") (pintype "passive"))
      (node (ref "R21") (pin "2") (pinfunction "2_2") (pintype "passive"))
    )
    (net (code "21") (name "N$18") (class "Default")
      (node (ref "R22") (pin "1") (pinfunction "1_1") (pintype "passive"))
      (node (ref "U1") (pin "4") (pinfunction "Q_4") (pintype "output"))
    )
    (net (code "22") (name "NRST") (class "Default")
      (node (ref "C13") (pin "P$2") (pinfunction "2_P$2") (pintype "passive"))
      (node (ref "J3") (pin "12") (pinfunction "12_12") (pintype "passive"))
      (node (ref "R28") (pin "1") (pinfunction "1_1") (pintype "passive"))
      (node (ref "S3") (pin "P$1") (pinfunction "P$1_P$1") (pintype "bidirectional"))
      (node (ref "S3") (pin "P$2") (pinfunction "P$1_P$2") (pintype "bidirectional"))
      (node (ref "U3") (pin "7") (pinfunction "NRST_7") (pintype "input"))
    )
    (net (code "23") (name "Net-(C1-1)") (class "Default")
      (node (ref "C1") (pin "P$1") (pinfunction "1_P$1") (pintype "passive"))
      (node (ref "J1") (pin "M1") (pinfunction "SHIELD_M1") (pintype "power_in"))
      (node (ref "J1") (pin "M2") (pinfunction "SHIELD_M2") (pintype "power_in"))
      (node (ref "R1") (pin "1") (pinfunction "1_1") (pintype "passive"))
    )
    (net (code "24") (name "Net-(C19-1)") (class "Default")
      (node (ref "C19") (pin "P$1") (pinfunction "1_P$1") (pintype "passive"))
      (node (ref "C20") (pin "P$1") (pinfunction "1_P$1") (pintype "passive"))
      (node (ref "SJ6") (pin "2") (pinfunction "2_2") (pintype "passive"))
      (node (ref "U4") (pin "5") (pinfunction "OUT_5") (pintype "power_in"))
    )
    (net (code "25") (name "Net-(C26-1)") (class "Default")
      (node (ref "C26") (pin "P$1") (pinfunction "1_P$1") (pintype "passive"))
      (node (ref "C28") (pin "P$1") (pinfunction "1_P$1") (pintype "passive"))
      (node (ref "SJ16") (pin "2") (pinfunction "2_2") (pintype "passive"))
      (node (ref "TP3") (pin "TP") (pinfunction "TP_TP") (pintype "input"))
      (node (ref "U6") (pin "5") (pinfunction "OUT_5") (pintype "power_in"))
    )
    (net (code "26") (name "Net-(C29-1)") (class "Default")
      (node (ref "C29") (pin "P$1") (pinfunction "1_P$1") (pintype "passive"))
      (node (ref "R23") (pin "1") (pinfunction "1_1") (pintype "passive"))
      (node (ref "R3") (pin "2") (pinfunction "2_2") (pintype "passive"))
      (node (ref "U7") (pin "3") (pinfunction "+IN_3") (pintype "input"))
    )
    (net (code "27") (name "Net-(C30-1)") (class "Default")
      (node (ref "C30") (pin "P$1") (pinfunction "1_P$1") (pintype "passive"))
      (node (ref "R6") (pin "2") (pinfunction "2_2") (pintype "passive"))
      (node (ref "R8") (pin "1") (pinfunction "1_1") (pintype "passive"))
      (node (ref "U7") (pin "2") (pinfunction "-IN_2") (pintype "input"))
    )
    (net (code "28") (name "Net-(C30-2)") (class "Default")
      (node (ref "C30") (pin "P$2") (pinfunction "2_P$2") (pintype "passive"))
      (node (ref "R7") (pin "1") (pinfunction "1_1") (pintype "passive"))
      (node (ref "R9") (pin "2") (pinfunction "2_2") (pintype "passive"))
      (node (ref "U7") (pin "1") (pinfunction "OUT_1") (pintype "output"))
    )
    (net (code "29") (name "Net-(C31-1)") (class "Default")
      (node (ref "C31") (pin "P$1") (pinfunction "1_P$1") (pintype "passive"))
      (node (ref "R10") (pin "2") (pinfunction "2_2") (pintype "passive"))
      (node (ref "R11") (pin "2") (pinfunction "2_2") (pintype "passive"))
      (node (ref "R9") (pin "1") (pinfunction "1_1") (pintype "passive"))
    )
    (net (code "30") (name "Net-(C32-1)") (class "Default")
      (node (ref "C32") (pin "P$1") (pinfunction "1_P$1") (pintype "passive"))
      (node (ref "R10") (pin "1") (pinfunction "1_1") (pintype "passive"))
      (node (ref "U7") (pin "14") (pinfunction "OUT_14") (pintype "output"))
    )
    (net (code "31") (name "Net-(C32-2)") (class "Default")
      (node (ref "C32") (pin "P$2") (pinfunction "2_P$2") (pintype "passive"))
      (node (ref "R11") (pin "1") (pinfunction "1_1") (pintype "passive"))
      (node (ref "U7") (pin "13") (pinfunction "-IN_13") (pintype "input"))
    )
    (net (code "32") (name "Net-(C79-1)") (class "Default")
      (node (ref "C79") (pin "P$1") (pinfunction "1_P$1") (pintype "passive"))
      (node (ref "R111") (pin "1") (pinfunction "1_1") (pintype "passive"))
      (node (ref "U6") (pin "3") (pinfunction "EN_3") (pintype "input"))
    )
    (net (code "33") (name "Net-(D3-P$1)") (class "Default")
      (node (ref "D3") (pin "A") (pinfunction "P$1_A") (pintype "bidirectional"))
      (node (ref "J1") (pin "3") (pinfunction "D+_3") (pintype "bidirectional"))
      (node (ref "U2") (pin "4") (pinfunction "D+_4") (pintype "bidirectional"))
    )
    (net (code "34") (name "Net-(D4-P$1)") (class "Default")
      (node (ref "D4") (pin "A") (pinfunction "P$1_A") (pintype "bidirectional"))
      (node (ref "J1") (pin "2") (pinfunction "D-_2") (pintype "bidirectional"))
      (node (ref "U2") (pin "5") (pinfunction "D-_5") (pintype "bidirectional"))
    )
    (net (code "35") (name "Net-(D10-PadA)") (class "Default")
      (node (ref "D10") (pin "A") (pinfunction "A_A") (pintype "passive"))
      (node (ref "R5") (pin "2") (pinfunction "2_2") (pintype "passive"))
    )
    (net (code "36") (name "Net-(D11-PadA)") (class "Default")
      (node (ref "D11") (pin "A") (pinfunction "A_A") (pintype "passive"))
      (node (ref "R22") (pin "2") (pinfunction "2_2") (pintype "passive"))
    )
    (net (code "37") (name "Net-(D12-PadA)") (class "Default")
      (node (ref "D12") (pin "A") (pinfunction "A_A") (pintype "passive"))
      (node (ref "R36") (pin "2") (pinfunction "2_2") (pintype "passive"))
    )
    (net (code "38") (name "Net-(R3-Pad1)") (class "Default")
      (node (ref "R3") (pin "1") (pinfunction "1_1") (pintype "passive"))
      (node (ref "R4") (pin "2") (pinfunction "2_2") (pintype "passive"))
    )
    (net (code "39") (name "Net-(R6-Pad1)") (class "Default")
      (node (ref "R6") (pin "1") (pinfunction "1_1") (pintype "passive"))
      (node (ref "R7") (pin "2") (pinfunction "2_2") (pintype "passive"))
    )
    (net (code "40") (name "Net-(R23-Pad2)") (class "Default")
      (node (ref "R23") (pin "2") (pinfunction "2_2") (pintype "passive"))
      (node (ref "SJ1") (pin "NC") (pinfunction "NC_NC") (pintype "passive"))
    )
    (net (code "41") (name "Net-(U$6-RING)") (class "Default")
      (node (ref "SJ1") (pin "COM") (pinfunction "COM_COM") (pintype "passive"))
      (node (ref "U$6") (pin "1") (pinfunction "SLEEVE_1") (pintype "passive"))
      (node (ref "U$6") (pin "3") (pinfunction "RING_3") (pintype "passive"))
    )
    (net (code "42") (name "Net-(U$6-TIP)") (class "Default")
      (node (ref "R8") (pin "2") (pinfunction "2_2") (pintype "passive"))
      (node (ref "U$6") (pin "2") (pinfunction "TIP_2") (pintype "passive"))
    )
    (net (code "43") (name "Net-(U2-~{RST})") (class "Default")
      (node (ref "R17") (pin "2") (pinfunction "2_2") (pintype "passive"))
      (node (ref "U2") (pin "9") (pinfunction "~{RST}_9") (pintype "bidirectional"))
    )
    (net (code "44") (name "Net-(U8A-AMP_BIAS)") (class "Default")
      (node (ref "R14") (pin "2") (pinfunction "2_2") (pintype "passive"))
      (node (ref "U8") (pin "1") (pinfunction "AMP_BIAS_1") (pintype "bidirectional"))
    )
    (net (code "45") (name "Net-(U8A-B)") (class "Default")
      (node (ref "R12") (pin "1") (pinfunction "1_1") (pintype "passive"))
      (node (ref "U8") (pin "5") (pinfunction "OUT_5") (pintype "bidirectional"))
      (node (ref "U8") (pin "7") (pinfunction "B_7") (pintype "passive"))
    )
    (net (code "46") (name "Net-(U8A-E)") (class "Default")
      (node (ref "R13") (pin "1") (pinfunction "1_1") (pintype "passive"))
      (node (ref "U8") (pin "8") (pinfunction "E_8") (pintype "passive"))
    )
    (net (code "47") (name "ON_MODE") (class "Default")
      (node (ref "R24") (pin "1") (pinfunction "1_1") (pintype "passive"))
      (node (ref "SW1") (pin "P$1") (pinfunction "P$1_P$1") (pintype "passive"))
      (node (ref "U3") (pin "2") (pinfunction "PC13_2") (pintype "bidirectional"))
    )
    (net (code "48") (name "OSC2_IN") (class "Default")
      (node (ref "C9") (pin "P$1") (pinfunction "1_P$1") (pintype "passive"))
      (node (ref "U3") (pin "5") (pinfunction "PF0/OSC_IN_5") (pintype "bidirectional"))
      (node (ref "XTAL1") (pin "P$3") (pinfunction "X2_P$3") (pintype "passive"))
    )
    (net (code "49") (name "OSC2_OUT") (class "Default")
      (node (ref "C10") (pin "P$1") (pinfunction "1_P$1") (pintype "passive"))
      (node (ref "U3") (pin "6") (pinfunction "PF1/OSC_OUT_6") (pintype "bidirectional"))
      (node (ref "XTAL1") (pin "P$1") (pinfunction "X1_P$1") (pintype "passive"))
    )
    (net (code "50") (name "PV") (class "Default")
      (node (ref "U3") (pin "28") (pinfunction "PD8_28") (pintype "bidirectional"))
    )
    (net (code "51") (name "RS_MODE") (class "Default")
      (node (ref "R25") (pin "1") (pinfunction "1_1") (pintype "passive"))
      (node (ref "SW1") (pin "P$3") (pinfunction "P$3_P$3") (pintype "passive"))
      (node (ref "U3") (pin "3") (pinfunction "PC14/OSC32_IN_3") (pintype "bidirectional"))
    )
    (net (code "52") (name "RXD") (class "Default")
      (node (ref "U2") (pin "25") (pinfunction "RXD_25") (pintype "input"))
      (node (ref "U5") (pin "2") (pinfunction "OUT_A_2") (pintype "output"))
    )
    (net (code "53") (name "SP1") (class "Default")
      (node (ref "U3") (pin "19") (pinfunction "PB1_19") (pintype "bidirectional"))
    )
    (net (code "54") (name "SP_MODE") (class "Default")
      (node (ref "R26") (pin "1") (pinfunction "1_1") (pintype "passive"))
      (node (ref "SW1") (pin "P$5") (pinfunction "P$5_P$5") (pintype "passive"))
      (node (ref "U3") (pin "4") (pinfunction "PC15/OSC32_OUT_4") (pintype "bidirectional"))
    )
    (net (code "55") (name "TXD") (class "Default")
      (node (ref "U2") (pin "26") (pinfunction "TXD_26") (pintype "output"))
      (node (ref "U5") (pin "3") (pinfunction "IN_B_3") (pintype "input"))
    )
    (net (code "56") (name "USART_RX") (class "Default")
      (node (ref "R15") (pin "2") (pinfunction "2_2") (pintype "passive"))
      (node (ref "R20") (pin "1") (pinfunction "1_1") (pintype "passive"))
      (node (ref "U3") (pin "31") (pinfunction "PA10_31") (pintype "bidirectional"))
    )
    (net (code "57") (name "USART_TX") (class "Default")
      (node (ref "R16") (pin "2") (pinfunction "2_2") (pintype "passive"))
      (node (ref "R21") (pin "1") (pinfunction "1_1") (pintype "passive"))
      (node (ref "U3") (pin "30") (pinfunction "PA9_30") (pintype "bidirectional"))
    )
    (net (code "58") (name "USB_DET") (class "Default")
      (node (ref "R18") (pin "1") (pinfunction "1_1") (pintype "passive"))
      (node (ref "R19") (pin "1") (pinfunction "1_1") (pintype "passive"))
      (node (ref "U2") (pin "8") (pinfunction "VBUS_8") (pintype "input"))
    )
    (net (code "59") (name "USB_RXD") (class "Default")
      (node (ref "R16") (pin "1") (pinfunction "1_1") (pintype "passive"))
      (node (ref "U5") (pin "7") (pinfunction "INA_A_7") (pintype "input"))
    )
    (net (code "60") (name "USB_TXD") (class "Default")
      (node (ref "R15") (pin "1") (pinfunction "1_1") (pintype "passive"))
      (node (ref "U5") (pin "6") (pinfunction "OUT_B_6") (pintype "output"))
    )
    (net (code "61") (name "VBAT") (class "Default")
      (node (ref "U3") (pin "1") (pinfunction "VBAT_1") (pintype "power_in"))
    )
    (net (code "62") (name "VDD_BRIDGE") (class "Default")
      (node (ref "C5") (pin "P$1") (pinfunction "1_P$1") (pintype "passive"))
      (node (ref "C6") (pin "P$1") (pinfunction "1_P$1") (pintype "passive"))
      (node (ref "R17") (pin "1") (pinfunction "1_1") (pintype "passive"))
      (node (ref "U2") (pin "6") (pinfunction "VDD_6") (pintype "power_in"))
    )
    (net (code "63") (name "VUSB") (class "Default")
      (node (ref "C21") (pin "P$1") (pinfunction "1_P$1") (pintype "passive"))
      (node (ref "C24") (pin "P$1") (pinfunction "1_P$1") (pintype "passive"))
      (node (ref "C4") (pin "P$1") (pinfunction "1_P$1") (pintype "passive"))
      (node (ref "C7") (pin "P$1") (pinfunction "1_P$1") (pintype "passive"))
      (node (ref "C8") (pin "P$1") (pinfunction "1_P$1") (pintype "passive"))
      (node (ref "D2") (pin "A") (pinfunction "P$1_A") (pintype "bidirectional"))
      (node (ref "J1") (pin "1") (pinfunction "VCC_1") (pintype "power_in"))
      (node (ref "PS1") (pin "+VIN") (pinfunction "+VIN_+VIN") (pintype "passive"))
      (node (ref "PS2") (pin "+VIN") (pinfunction "+VIN_+VIN") (pintype "passive"))
      (node (ref "R19") (pin "2") (pinfunction "2_2") (pintype "passive"))
      (node (ref "U2") (pin "7") (pinfunction "REGIN_7") (pintype "power_in"))
      (node (ref "U5") (pin "1") (pinfunction "VCC1_1") (pintype "power_in"))
    )
    (net (code "64") (name "unconnected-(J3-Pad01)") (class "Default")
      (node (ref "J3") (pin "01") (pinfunction "01_01") (pintype "passive"))
    )
    (net (code "65") (name "unconnected-(J3-Pad02)") (class "Default")
      (node (ref "J3") (pin "02") (pinfunction "02_02") (pintype "passive"))
    )
    (net (code "66") (name "unconnected-(J3-Pad11)") (class "Default")
      (node (ref "J3") (pin "11") (pinfunction "11_11") (pintype "passive"))
    )
    (net (code "67") (name "unconnected-(U2-CHR0-Pad15)") (class "Default")
      (node (ref "U2") (pin "15") (pinfunction "CHR0_15") (pintype "output"))
    )
    (net (code "68") (name "unconnected-(U2-CHR1-Pad14)") (class "Default")
      (node (ref "U2") (pin "14") (pinfunction "CHR1_14") (pintype "output"))
    )
    (net (code "69") (name "unconnected-(U2-CHREN-Pad13)") (class "Default")
      (node (ref "U2") (pin "13") (pinfunction "CHREN_13") (pintype "output"))
    )
    (net (code "70") (name "unconnected-(U2-CTS-Pad23)") (class "Default")
      (node (ref "U2") (pin "23") (pinfunction "CTS_23") (pintype "input"))
    )
    (net (code "71") (name "unconnected-(U2-DCD-Pad1)") (class "Default")
      (node (ref "U2") (pin "1") (pinfunction "DCD_1") (pintype "input"))
    )
    (net (code "72") (name "unconnected-(U2-DSR-Pad27)") (class "Default")
      (node (ref "U2") (pin "27") (pinfunction "DSR_27") (pintype "input"))
    )
    (net (code "73") (name "unconnected-(U2-DTR-Pad28)") (class "Default")
      (node (ref "U2") (pin "28") (pinfunction "DTR_28") (pintype "output"))
    )
    (net (code "74") (name "unconnected-(U2-GPIO0{slash}TXT-Pad19)") (class "Default")
      (node (ref "U2") (pin "19") (pinfunction "GPIO0/TXT_19") (pintype "bidirectional"))
    )
    (net (code "75") (name "unconnected-(U2-GPIO1{slash}RXT-Pad18)") (class "Default")
      (node (ref "U2") (pin "18") (pinfunction "GPIO1/RXT_18") (pintype "bidirectional"))
    )
    (net (code "76") (name "unconnected-(U2-GPIO2{slash}RS485-Pad17)") (class "Default")
      (node (ref "U2") (pin "17") (pinfunction "GPIO2/RS485_17") (pintype "bidirectional"))
    )
    (net (code "77") (name "unconnected-(U2-GPIO3{slash}WAKEUP-Pad16)") (class "Default")
      (node (ref "U2") (pin "16") (pinfunction "GPIO3/WAKEUP_16") (pintype "bidirectional"))
    )
    (net (code "78") (name "unconnected-(U2-GPIO4-Pad22)") (class "Default")
      (node (ref "U2") (pin "22") (pinfunction "GPIO4_22") (pintype "bidirectional"))
    )
    (net (code "79") (name "unconnected-(U2-GPIO5-Pad21)") (class "Default")
      (node (ref "U2") (pin "21") (pinfunction "GPIO5_21") (pintype "bidirectional"))
    )
    (net (code "80") (name "unconnected-(U2-GPIO6-Pad20)") (class "Default")
      (node (ref "U2") (pin "20") (pinfunction "GPIO6_20") (pintype "bidirectional"))
    )
    (net (code "81") (name "unconnected-(U2-RI-Pad2)") (class "Default")
      (node (ref "U2") (pin "2") (pinfunction "RI_2") (pintype "bidirectional"))
    )
    (net (code "82") (name "unconnected-(U2-RTS-Pad24)") (class "Default")
      (node (ref "U2") (pin "24") (pinfunction "RTS_24") (pintype "output"))
    )
    (net (code "83") (name "unconnected-(U2-SUSPEND-Pad12)") (class "Default")
      (node (ref "U2") (pin "12") (pinfunction "SUSPEND_12") (pintype "output"))
    )
    (net (code "84") (name "unconnected-(U2-~{SUSPEND}-Pad11)") (class "Default")
      (node (ref "U2") (pin "11") (pinfunction "~{SUSPEND}_11") (pintype "output"))
    )
    (net (code "85") (name "unconnected-(U3-PA0-Pad10)") (class "Default")
      (node (ref "U3") (pin "10") (pinfunction "PA0_10") (pintype "bidirectional"))
    )
    (net (code "86") (name "unconnected-(U3-PA1-Pad11)") (class "Default")
      (node (ref "U3") (pin "11") (pinfunction "PA1_11") (pintype "bidirectional"))
    )
    (net (code "87") (name "unconnected-(U3-PA2-Pad12)") (class "Default")
      (node (ref "U3") (pin "12") (pinfunction "PA2_12") (pintype "bidirectional"))
    )
    (net (code "88") (name "unconnected-(U3-PA3-Pad13)") (class "Default")
      (node (ref "U3") (pin "13") (pinfunction "PA3_13") (pintype "bidirectional"))
    )
    (net (code "89") (name "unconnected-(U3-PA4-Pad14)") (class "Default")
      (node (ref "U3") (pin "14") (pinfunction "PA4_14") (pintype "bidirectional"))
    )
    (net (code "90") (name "unconnected-(U3-PA5-Pad15)") (class "Default")
      (node (ref "U3") (pin "15") (pinfunction "PA5_15") (pintype "bidirectional"))
    )
    (net (code "91") (name "unconnected-(U3-PA6-Pad16)") (class "Default")
      (node (ref "U3") (pin "16") (pinfunction "PA6_16") (pintype "bidirectional"))
    )
    (net (code "92") (name "unconnected-(U3-PA8-Pad29)") (class "Default")
      (node (ref "U3") (pin "29") (pinfunction "PA8_29") (pintype "bidirectional"))
    )
    (net (code "93") (name "unconnected-(U3-PA11-Pad32)") (class "Default")
      (node (ref "U3") (pin "32") (pinfunction "PA11_32") (pintype "bidirectional"))
    )
    (net (code "94") (name "unconnected-(U3-PA12-Pad33)") (class "Default")
      (node (ref "U3") (pin "33") (pinfunction "PA12_33") (pintype "bidirectional"))
    )
    (net (code "95") (name "unconnected-(U3-PB0-Pad18)") (class "Default")
      (node (ref "U3") (pin "18") (pinfunction "PB0_18") (pintype "bidirectional"))
    )
    (net (code "96") (name "unconnected-(U3-PB2-Pad20)") (class "Default")
      (node (ref "U3") (pin "20") (pinfunction "PB2_20") (pintype "bidirectional"))
    )
    (net (code "97") (name "unconnected-(U3-PB4-Pad40)") (class "Default")
      (node (ref "U3") (pin "40") (pinfunction "PB4_40") (pintype "bidirectional"))
    )
    (net (code "98") (name "unconnected-(U3-PB5-Pad41)") (class "Default")
      (node (ref "U3") (pin "41") (pinfunction "PB5_41") (pintype "bidirectional"))
    )
    (net (code "99") (name "unconnected-(U3-PB6-Pad42)") (class "Default")
      (node (ref "U3") (pin "42") (pinfunction "PB6_42") (pintype "bidirectional"))
    )
    (net (code "100") (name "unconnected-(U3-PB7-Pad43)") (class "Default")
      (node (ref "U3") (pin "43") (pinfunction "PB7_43") (pintype "bidirectional"))
    )
    (net (code "101") (name "unconnected-(U3-PB14-Pad26)") (class "Default")
      (node (ref "U3") (pin "26") (pinfunction "PB14_26") (pintype "bidirectional"))
    )
    (net (code "102") (name "unconnected-(U3-PB15-Pad27)") (class "Default")
      (node (ref "U3") (pin "27") (pinfunction "PB15_27") (pintype "bidirectional"))
    )
    (net (code "103") (name "unconnected-(U3-PE8-Pad21)") (class "Default")
      (node (ref "U3") (pin "21") (pinfunction "PE8_21") (pintype "bidirectional"))
    )
    (net (code "104") (name "unconnected-(U3-PE9-Pad22)") (class "Default")
      (node (ref "U3") (pin "22") (pinfunction "PE9_22") (pintype "bidirectional"))
    )
    (net (code "105") (name "unconnected-(U3-PF6-Pad35)") (class "Default")
      (node (ref "U3") (pin "35") (pinfunction "PF6_35") (pintype "bidirectional"))
    )
    (net (code "106") (name "unconnected-(U3-PF7-Pad36)") (class "Default")
      (node (ref "U3") (pin "36") (pinfunction "PF7_36") (pintype "bidirectional"))
    )
    (net (code "107") (name "unconnected-(U4-N{slash}C-Pad4)") (class "Default")
      (node (ref "U4") (pin "4") (pinfunction "N/C_4") (pintype "no_connect"))
    )
    (net (code "108") (name "unconnected-(U6-N{slash}C-Pad4)") (class "Default")
      (node (ref "U6") (pin "4") (pinfunction "N/C_4") (pintype "no_connect"))
    )
    (net (code "109") (name "unconnected-(U7B-+IN-Pad5)") (class "Default")
      (node (ref "U7") (pin "5") (pinfunction "+IN_5") (pintype "input"))
    )
    (net (code "110") (name "unconnected-(U7B--IN-Pad6)") (class "Default")
      (node (ref "U7") (pin "6") (pinfunction "-IN_6") (pintype "input"))
    )
    (net (code "111") (name "unconnected-(U7B-OUT-Pad7)") (class "Default")
      (node (ref "U7") (pin "7") (pinfunction "OUT_7") (pintype "output"))
    )
    (net (code "112") (name "unconnected-(U7C-+IN-Pad10)") (class "Default")
      (node (ref "U7") (pin "10") (pinfunction "+IN_10") (pintype "input"))
    )
    (net (code "113") (name "unconnected-(U7C--IN-Pad9)") (class "Default")
      (node (ref "U7") (pin "9") (pinfunction "-IN_9") (pintype "input"))
    )
    (net (code "114") (name "unconnected-(U7C-OUT-Pad8)") (class "Default")
      (node (ref "U7") (pin "8") (pinfunction "OUT_8") (pintype "output"))
    )
    (net (code "115") (name "unconnected-(U8A-+-Pad3)") (class "Default")
      (node (ref "U8") (pin "3") (pinfunction "+_3") (pintype "bidirectional"))
    )
    (net (code "116") (name "unconnected-(U8A---Pad4)") (class "Default")
      (node (ref "U8") (pin "4") (pinfunction "-_4") (pintype "bidirectional"))
    )
    (net (code "117") (name "unconnected-(U8A-D_BIAS-Pad2)") (class "Default")
      (node (ref "U8") (pin "2") (pinfunction "D_BIAS_2") (pintype "bidirectional"))
    )
    (net (code "118") (name "unconnected-(U8B-+-Pad14)") (class "Default")
      (node (ref "U8") (pin "14") (pinfunction "+_14") (pintype "bidirectional"))
    )
    (net (code "119") (name "unconnected-(U8B---Pad13)") (class "Default")
      (node (ref "U8") (pin "13") (pinfunction "-_13") (pintype "bidirectional"))
    )
    (net (code "120") (name "unconnected-(U8B-AMP_BIAS-Pad16)") (class "Default")
      (node (ref "U8") (pin "16") (pinfunction "AMP_BIAS_16") (pintype "bidirectional"))
    )
    (net (code "121") (name "unconnected-(U8B-B-Pad10)") (class "Default")
      (node (ref "U8") (pin "10") (pinfunction "B_10") (pintype "passive"))
    )
    (net (code "122") (name "unconnected-(U8B-D_BIAS-Pad15)") (class "Default")
      (node (ref "U8") (pin "15") (pinfunction "D_BIAS_15") (pintype "bidirectional"))
    )
    (net (code "123") (name "unconnected-(U8B-E-Pad9)") (class "Default")
      (node (ref "U8") (pin "9") (pinfunction "E_9") (pintype "passive"))
    )
    (net (code "124") (name "unconnected-(U8B-OUT-Pad12)") (class "Default")
      (node (ref "U8") (pin "12") (pinfunction "OUT_12") (pintype "bidirectional"))
    )
  )
)
